# PLT-01-RevA.net
KiCad netlist of a schematic drawn in EAGLE
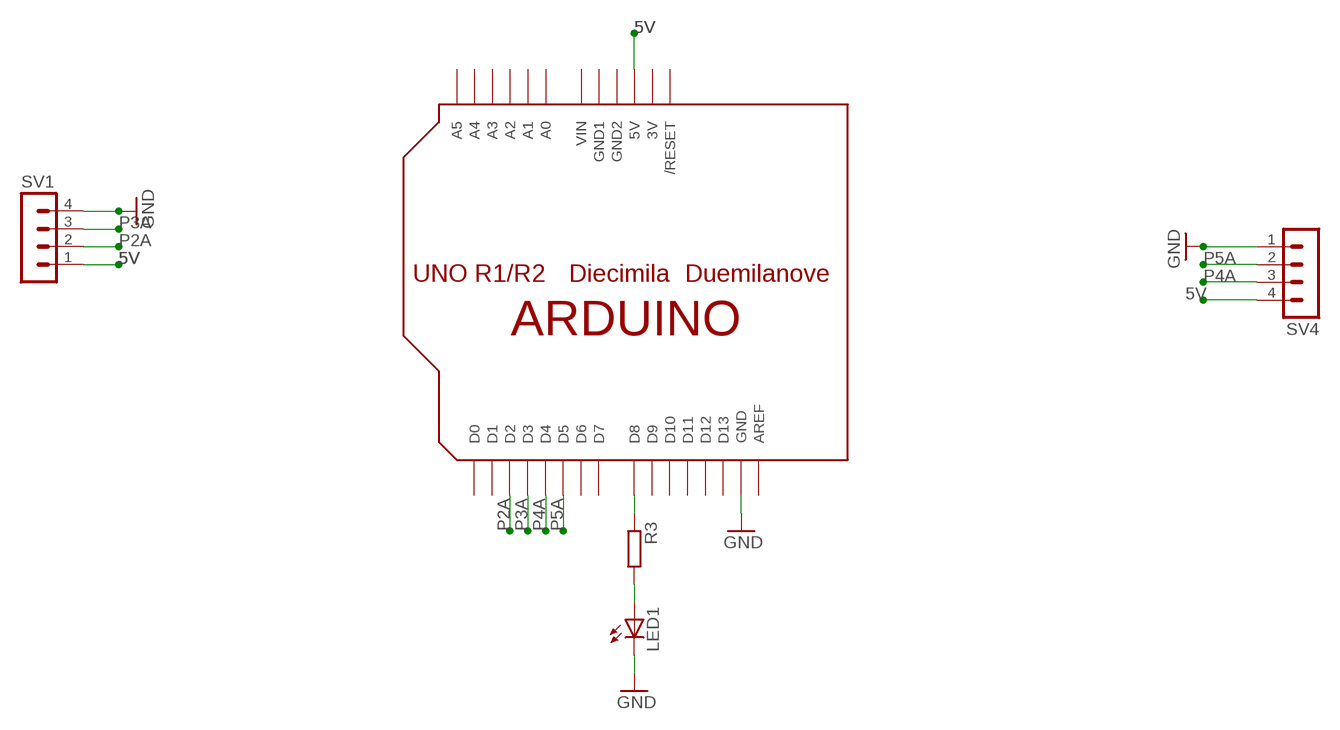
[diagram p0: schematic, sheet 1]

(export (version "E")
  (design (tool "Eeschema 10.0.6"))
  (components
    (comp (ref "LED1")
      (value "LED5MM")
      (footprint "eagle-import:LED5MM")
      (libsource (lib "eagle-import") (part "LED5MM"))
    )
    (comp (ref "R3")
      (value "R-EU_0207/10")
      (footprint "eagle-import:0207_10")
      (libsource (lib "eagle-import") (part "R-EU_0207/10"))
    )
    (comp (ref "SV1")
      (value "MA04-1")
      (footprint "eagle-import:MA04-1")
      (libsource (lib "eagle-import") (part "MA04-1"))
    )
    (comp (ref "SV4")
      (value "MA04-1")
      (footprint "eagle-import:MA04-1")
      (libsource (lib "eagle-import") (part "MA04-1"))
    )
    (comp (ref "U$1")
      (value "ARDUINOUNO")
      (footprint "eagle-import:ARDUINO")
      (libsource (lib "eagle-import") (part "ARDUINOUNO"))
    )
  )
  (nets
    (net (code "1") (name "/3V") (class "Default")
      (node (ref "U$1") (pin "3V") (pinfunction "3V_3V") (pintype "power_in"))
    )
    (net (code "2") (name "/5V") (class "Default")
      (node (ref "SV1") (pin "1") (pinfunction "1_1") (pintype "passive"))
      (node (ref "SV4") (pin "4") (pinfunction "4_4") (pintype "passive"))
      (node (ref "U$1") (pin "5V") (pinfunction "5V_5V") (pintype "power_in"))
    )
    (net (code "3") (name "/GND1") (class "Default")
      (node (ref "U$1") (pin "GND1") (pinfunction "GND1_GND1") (pintype "power_in"))
    )
    (net (code "4") (name "/GND2") (class "Default")
      (node (ref "U$1") (pin "GND2") (pinfunction "GND2_GND2") (pintype "power_in"))
    )
    (net (code "5") (name "/P2A") (class "Default")
      (node (ref "SV1") (pin "2") (pinfunction "2_2") (pintype "passive"))
      (node (ref "U$1") (pin "D2") (pinfunction "D2_D2") (pintype "bidirectional"))
    )
    (net (code "6") (name "/P3A") (class "Default")
      (node (ref "SV1") (pin "3") (pinfunction "3_3") (pintype "passive"))
      (node (ref "U$1") (pin "D3") (pinfunction "D3_D3") (pintype "bidirectional"))
    )
    (net (code "7") (name "/P4A") (class "Default")
      (node (ref "SV4") (pin "3") (pinfunction "3_3") (pintype "passive"))
      (node (ref "U$1") (pin "D4") (pinfunction "D4_D4") (pintype "bidirectional"))
    )
    (net (code "8") (name "/P5A") (class "Default")
      (node (ref "SV4") (pin "2") (pinfunction "2_2") (pintype "passive"))
      (node (ref "U$1") (pin "D5") (pinfunction "D5_D5") (pintype "bidirectional"))
    )
    (net (code "9") (name "/VIN") (class "Default")
      (node (ref "U$1") (pin "VIN") (pinfunction "VIN_VIN") (pintype "power_in"))
    )
    (net (code "10") (name "GND") (class "Default")
      (node (ref "LED1") (pin "K") (pinfunction "C_K") (pintype "passive"))
      (node (ref "SV1") (pin "4") (pinfunction "4_4") (pintype "passive"))
      (node (ref "SV4") (pin "1") (pinfunction "1_1") (pintype "passive"))
      (node (ref "U$1") (pin "GND") (pinfunction "GND_GND") (pintype "power_in"))
    )
    (net (code "11") (name "Net-(LED1-PadA)") (class "Default")
      (node (ref "LED1") (pin "A") (pinfunction "A_A") (pintype "passive"))
      (node (ref "R3") (pin "2") (pinfunction "2_2") (pintype "passive"))
    )
    (net (code "12") (name "Net-(R3-Pad1)") (class "Default")
      (node (ref "R3") (pin "1") (pinfunction "1_1") (pintype "passive"))
      (node (ref "U$1") (pin "D8") (pinfunction "D8_D8") (pintype "bidirectional"))
    )
    (net (code "13") (name "unconnected-(U$1-PadA0)") (class "Default")
      (node (ref "U$1") (pin "A0") (pinfunction "A0_A0") (pintype "bidirectional"))
    )
    (net (code "14") (name "unconnected-(U$1-PadA1)") (class "Default")
      (node (ref "U$1") (pin "A1") (pinfunction "A1_A1") (pintype "bidirectional"))
    )
    (net (code "15") (name "unconnected-(U$1-PadA2)") (class "Default")
      (node (ref "U$1") (pin "A2") (pinfunction "A2_A2") (pintype "bidirectional"))
    )
    (net (code "16") (name "unconnected-(U$1-PadA3)") (class "Default")
      (node (ref "U$1") (pin "A3") (pinfunction "A3_A3") (pintype "bidirectional"))
    )
    (net (code "17") (name "unconnected-(U$1-PadA4)") (class "Default")
      (node (ref "U$1") (pin "A4") (pinfunction "A4_A4") (pintype "bidirectional"))
    )
    (net (code "18") (name "unconnected-(U$1-PadA5)") (class "Default")
      (node (ref "U$1") (pin "A5") (pinfunction "A5_A5") (pintype "bidirectional"))
    )
    (net (code "19") (name "unconnected-(U$1-PadAREF)") (class "Default")
      (node (ref "U$1") (pin "AREF") (pinfunction "AREF_AREF") (pintype "bidirectional"))
    )
    (net (code "20") (name "unconnected-(U$1-PadD0)") (class "Default")
      (node (ref "U$1") (pin "D0") (pinfunction "D0_D0") (pintype "bidirectional"))
    )
    (net (code "21") (name "unconnected-(U$1-PadD1)") (class "Default")
      (node (ref "U$1") (pin "D1") (pinfunction "D1_D1") (pintype "bidirectional"))
    )
    (net (code "22") (name "unconnected-(U$1-PadD6)") (class "Default")
      (node (ref "U$1") (pin "D6") (pinfunction "D6_D6") (pintype "bidirectional"))
    )
    (net (code "23") (name "unconnected-(U$1-PadD7)") (class "Default")
      (node (ref "U$1") (pin "D7") (pinfunction "D7_D7") (pintype "bidirectional"))
    )
    (net (code "24") (name "unconnected-(U$1-PadD9)") (class "Default")
      (node (ref "U$1") (pin "D9") (pinfunction "D9_D9") (pintype "bidirectional"))
    )
    (net (code "25") (name "unconnected-(U$1-PadD10)") (class "Default")
      (node (ref "U$1") (pin "D10") (pinfunction "D10_D10") (pintype "bidirectional"))
    )
    (net (code "26") (name "unconnected-(U$1-PadD11)") (class "Default")
      (node (ref "U$1") (pin "D11") (pinfunction "D11_D11") (pintype "bidirectional"))
    )
    (net (code "27") (name "unconnected-(U$1-PadD12)") (class "Default")
      (node (ref "U$1") (pin "D12") (pinfunction "D12_D12") (pintype "bidirectional"))
    )
    (net (code "28") (name "unconnected-(U$1-PadD13)") (class "Default")
      (node (ref "U$1") (pin "D13") (pinfunction "D13_D13") (pintype "bidirectional"))
    )
    (net (code "29") (name "unconnected-(U$1-{slash}RESET-PadRESET)") (class "Default")
      (node (ref "U$1") (pin "RESET") (pinfunction "/RESET_RESET") (pintype "bidirectional"))
    )
  )
)
